# Detektor_hran.net
KiCad netlist of a schematic drawn in EAGLE
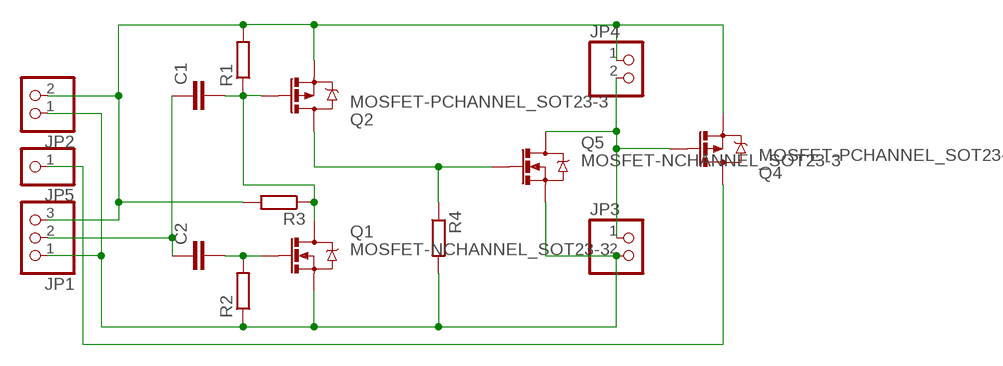
[diagram p0: schematic, sheet 1]

(export (version "E")
  (design (tool "Eeschema 10.0.6"))
  (components
    (comp (ref "C1")
      (value "C-EUC0805")
      (footprint "eagle-import:C0805")
      (libsource (lib "eagle-import") (part "C-EUC0805"))
    )
    (comp (ref "C2")
      (value "C-EUC0805")
      (footprint "eagle-import:C0805")
      (libsource (lib "eagle-import") (part "C-EUC0805"))
    )
    (comp (ref "JP1")
      (value "PINHD-1X03_2.54")
      (footprint "eagle-import:1X03")
      (libsource (lib "eagle-import") (part "PINHD-1X03_2.54"))
    )
    (comp (ref "JP2")
      (value "PINHD-1X02_2.54")
      (footprint "eagle-import:1X02")
      (libsource (lib "eagle-import") (part "PINHD-1X02_2.54"))
    )
    (comp (ref "JP3")
      (value "PINHD-1X02_2.54")
      (footprint "eagle-import:1X02")
      (libsource (lib "eagle-import") (part "PINHD-1X02_2.54"))
    )
    (comp (ref "JP4")
      (value "PINHD-1X02_2.54")
      (footprint "eagle-import:1X02")
      (libsource (lib "eagle-import") (part "PINHD-1X02_2.54"))
    )
    (comp (ref "JP5")
      (value "PINHD-1X01_2.54-90°")
      (footprint "eagle-import:1X01_90")
      (libsource (lib "eagle-import") (part "PINHD-1X01_2.54-90°"))
    )
    (comp (ref "Q1")
      (value "MOSFET-NCHANNEL_SOT23-3")
      (footprint "eagle-import:SOT23-3")
      (libsource (lib "eagle-import") (part "MOSFET-NCHANNEL_SOT23-3"))
    )
    (comp (ref "Q2")
      (value "MOSFET-PCHANNEL_SOT23-3")
      (footprint "eagle-import:SOT23-3")
      (libsource (lib "eagle-import") (part "MOSFET-PCHANNEL_SOT23-3"))
    )
    (comp (ref "Q4")
      (value "MOSFET-PCHANNEL_SOT23-3")
      (footprint "eagle-import:SOT23-3")
      (libsource (lib "eagle-import") (part "MOSFET-PCHANNEL_SOT23-3"))
    )
    (comp (ref "Q5")
      (value "MOSFET-NCHANNEL_SOT23-3")
      (footprint "eagle-import:SOT23-3")
      (libsource (lib "eagle-import") (part "MOSFET-NCHANNEL_SOT23-3"))
    )
    (comp (ref "R1")
      (value "R-EU_R0805")
      (footprint "eagle-import:R0805")
      (libsource (lib "eagle-import") (part "R-EU_R0805"))
    )
    (comp (ref "R2")
      (value "R-EU_R0805")
      (footprint "eagle-import:R0805")
      (libsource (lib "eagle-import") (part "R-EU_R0805"))
    )
    (comp (ref "R3")
      (value "R-EU_R0805")
      (footprint "eagle-import:R0805")
      (libsource (lib "eagle-import") (part "R-EU_R0805"))
    )
    (comp (ref "R4")
      (value "R-EU_R0805")
      (footprint "eagle-import:R0805")
      (libsource (lib "eagle-import") (part "R-EU_R0805"))
    )
  )
  (nets
    (net (code "1") (name "Net-(C1-Pad1)") (class "Default")
      (node (ref "C1") (pin "1") (pinfunction "1_1") (pintype "passive"))
      (node (ref "C2") (pin "1") (pinfunction "1_1") (pintype "passive"))
      (node (ref "JP1") (pin "2") (pinfunction "2_2") (pintype "passive"))
    )
    (net (code "2") (name "Net-(Q1-D)") (class "Default")
      (node (ref "C1") (pin "2") (pinfunction "2_2") (pintype "passive"))
      (node (ref "Q1") (pin "3") (pinfunction "D_3") (pintype "passive"))
      (node (ref "Q2") (pin "1") (pinfunction "G_1") (pintype "passive"))
      (node (ref "R1") (pin "1") (pinfunction "1_1") (pintype "passive"))
      (node (ref "R3") (pin "1") (pinfunction "1_1") (pintype "passive"))
    )
    (net (code "3") (name "Net-(Q1-G)") (class "Default")
      (node (ref "C2") (pin "2") (pinfunction "2_2") (pintype "passive"))
      (node (ref "Q1") (pin "1") (pinfunction "G_1") (pintype "passive"))
      (node (ref "R2") (pin "2") (pinfunction "2_2") (pintype "passive"))
    )
    (net (code "4") (name "Net-(Q1-S)") (class "Default")
      (node (ref "JP1") (pin "1") (pinfunction "1_1") (pintype "passive"))
      (node (ref "JP2") (pin "1") (pinfunction "1_1") (pintype "passive"))
      (node (ref "JP3") (pin "2") (pinfunction "2_2") (pintype "passive"))
      (node (ref "Q1") (pin "2") (pinfunction "S_2") (pintype "passive"))
      (node (ref "Q5") (pin "2") (pinfunction "S_2") (pintype "passive"))
      (node (ref "R2") (pin "1") (pinfunction "1_1") (pintype "passive"))
      (node (ref "R4") (pin "2") (pinfunction "2_2") (pintype "passive"))
    )
    (net (code "5") (name "Net-(Q2-D)") (class "Default")
      (node (ref "Q2") (pin "3") (pinfunction "D_3") (pintype "passive"))
      (node (ref "Q5") (pin "1") (pinfunction "G_1") (pintype "passive"))
      (node (ref "R4") (pin "1") (pinfunction "1_1") (pintype "passive"))
    )
    (net (code "6") (name "Net-(Q2-S)") (class "Default")
      (node (ref "JP1") (pin "3") (pinfunction "3_3") (pintype "passive"))
      (node (ref "JP2") (pin "2") (pinfunction "2_2") (pintype "passive"))
      (node (ref "JP4") (pin "1") (pinfunction "1_1") (pintype "passive"))
      (node (ref "Q2") (pin "2") (pinfunction "S_2") (pintype "passive"))
      (node (ref "Q4") (pin "2") (pinfunction "S_2") (pintype "passive"))
      (node (ref "R1") (pin "2") (pinfunction "2_2") (pintype "passive"))
      (node (ref "R3") (pin "2") (pinfunction "2_2") (pintype "passive"))
    )
    (net (code "7") (name "Net-(Q4-D)") (class "Default")
      (node (ref "JP5") (pin "1") (pinfunction "1_1") (pintype "passive"))
      (node (ref "Q4") (pin "3") (pinfunction "D_3") (pintype "passive"))
    )
    (net (code "8") (name "Net-(Q4-G)") (class "Default")
      (node (ref "JP3") (pin "1") (pinfunction "1_1") (pintype "passive"))
      (node (ref "JP4") (pin "2") (pinfunction "2_2") (pintype "passive"))
      (node (ref "Q4") (pin "1") (pinfunction "G_1") (pintype "passive"))
      (node (ref "Q5") (pin "3") (pinfunction "D_3") (pintype "passive"))
    )
  )
)
